# FORCE_SENSOR.net
KiCad netlist of a schematic drawn in EAGLE
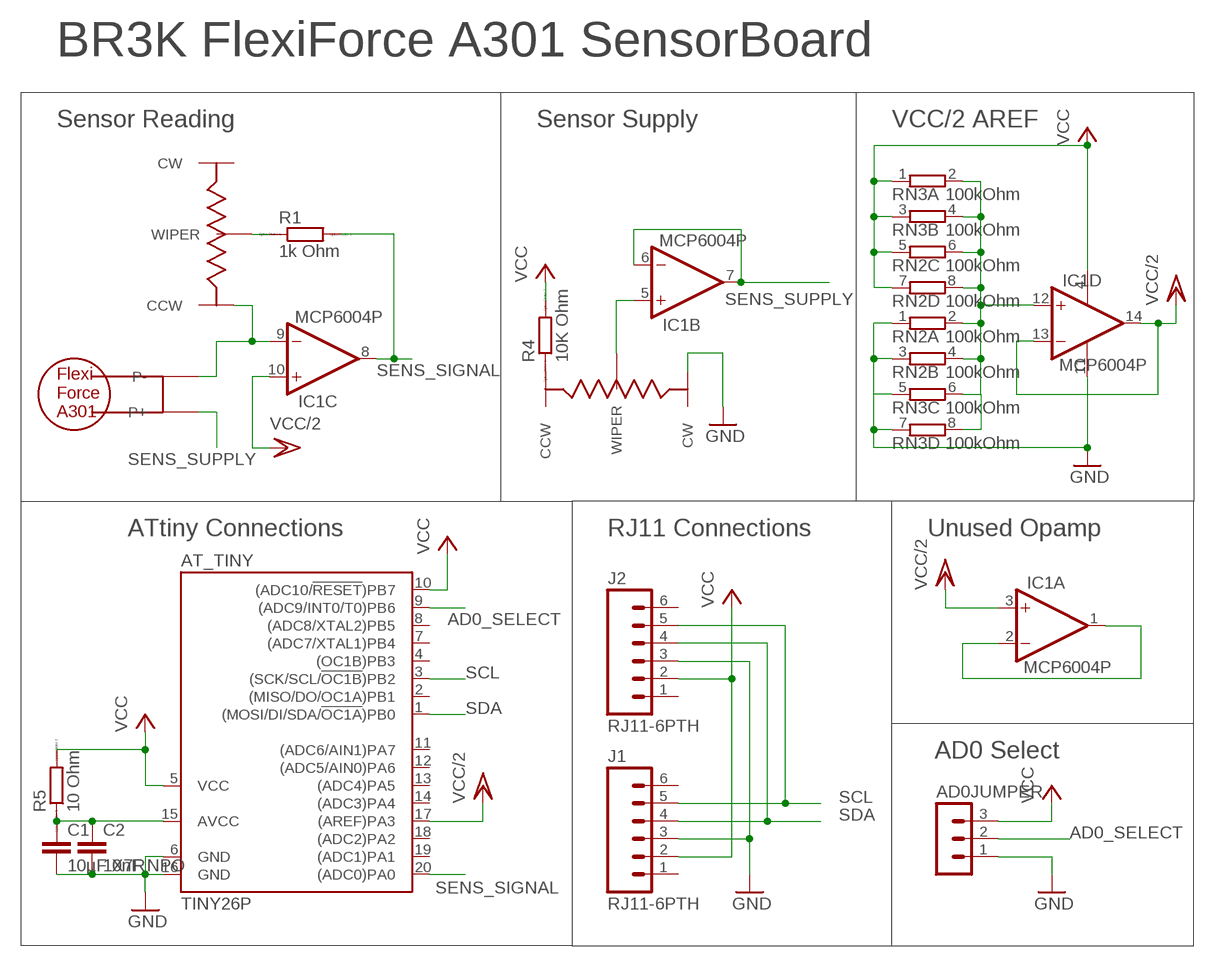
[diagram p0: schematic, sheet 1]

(export (version "E")
  (design (tool "Eeschema 10.0.6"))
  (components
    (comp (ref "AD0JUMPER")
      (value "MA03-1")
      (footprint "eagle-import:MA03-1")
      (libsource (lib "eagle-import") (part "MA03-1"))
    )
    (comp (ref "AT_TINY")
      (value "TINY26P")
      (footprint "eagle-import:DIL20")
      (fields (field (name "MPN") "ATTINY261-20PU"))
      (libsource (lib "eagle-import") (part "TINY26P"))
    )
    (comp (ref "C1")
      (value "10µF X7R")
      (footprint "eagle-import:C5B2.5")
      (libsource (lib "eagle-import") (part "C5/2.5"))
    )
    (comp (ref "C2")
      (value "10nF NPO")
      (footprint "eagle-import:C5B2.5")
      (libsource (lib "eagle-import") (part "C5/2.5"))
    )
    (comp (ref "IC1")
      (value "MCP6004P")
      (footprint "eagle-import:DIL14")
      (libsource (lib "eagle-import") (part "MCP6004P"))
    )
    (comp (ref "J1")
      (value "RJ11-6PTH")
      (footprint "eagle-import:RJ11-6")
      (libsource (lib "eagle-import") (part "RJ11-6PTH"))
    )
    (comp (ref "J2")
      (value "RJ11-6PTH")
      (footprint "eagle-import:RJ11-6")
      (libsource (lib "eagle-import") (part "RJ11-6PTH"))
    )
    (comp (ref "R1")
      (value "1k Ohm")
      (footprint "eagle-import:0207_10")
      (libsource (lib "eagle-import") (part "R-EU_0207_10"))
    )
    (comp (ref "R4")
      (value "10K Ohm")
      (footprint "eagle-import:0207_10")
      (libsource (lib "eagle-import") (part "R-EU_0207_10"))
    )
    (comp (ref "R5")
      (value "10 Ohm")
      (footprint "eagle-import:0207_10")
      (libsource (lib "eagle-import") (part "R-EU_0207_10"))
    )
    (comp (ref "RN2")
      (value "100kOhm")
      (footprint "eagle-import:SIL8")
      (libsource (lib "eagle-import") (part "E4R"))
    )
    (comp (ref "RN3")
      (value "100kOhm")
      (footprint "eagle-import:SIL8")
      (libsource (lib "eagle-import") (part "E4R"))
    )
    (comp (ref "U$1")
      (value "FLEXI_FORCE_A301")
      (footprint "eagle-import:FLEXIFORCE_W237-102")
      (libsource (lib "eagle-import") (part "FLEXI_FORCE_A301"))
    )
    (comp (ref "U$2")
      (value "100k Ohm")
      (footprint "eagle-import:VERT_TRIMPOT")
      (libsource (lib "eagle-import") (part "TRIMMER_3296"))
    )
    (comp (ref "U$3")
      (value "10k Ohm")
      (footprint "eagle-import:VERT_TRIMPOT")
      (libsource (lib "eagle-import") (part "TRIMMER_3296"))
    )
  )
  (nets
    (net (code "1") (name "/AD0_SELECT") (class "Default")
      (node (ref "AD0JUMPER") (pin "2") (pinfunction "2_2") (pintype "passive"))
      (node (ref "AT_TINY") (pin "9") (pinfunction "(ADC9/INT0/T0)PB6_9") (pintype "bidirectional"))
    )
    (net (code "2") (name "/SCL") (class "Default")
      (node (ref "AT_TINY") (pin "3") (pinfunction "(SCK/SCL/~{OC1B})PB2_3") (pintype "bidirectional"))
      (node (ref "J1") (pin "5") (pinfunction "5_5") (pintype "passive"))
      (node (ref "J2") (pin "5") (pinfunction "5_5") (pintype "passive"))
    )
    (net (code "3") (name "/SDA") (class "Default")
      (node (ref "AT_TINY") (pin "1") (pinfunction "(MOSI/DI/SDA/~{OC1A})PB0_1") (pintype "bidirectional"))
      (node (ref "J1") (pin "4") (pinfunction "4_4") (pintype "passive"))
      (node (ref "J2") (pin "4") (pinfunction "4_4") (pintype "passive"))
    )
    (net (code "4") (name "/SENS_SIGNAL") (class "Default")
      (node (ref "AT_TINY") (pin "20") (pinfunction "(ADC0)PA0_20") (pintype "bidirectional"))
      (node (ref "IC1") (pin "8") (pinfunction "OUT_8") (pintype "output"))
      (node (ref "R1") (pin "2") (pinfunction "2_2") (pintype "passive"))
    )
    (net (code "5") (name "/SENS_SUPPLY") (class "Default")
      (node (ref "IC1") (pin "6") (pinfunction "-IN_6") (pintype "input"))
      (node (ref "IC1") (pin "7") (pinfunction "OUT_7") (pintype "output"))
      (node (ref "U$1") (pin "1") (pinfunction "P+_1") (pintype "bidirectional"))
    )
    (net (code "6") (name "GND") (class "Default")
      (node (ref "AD0JUMPER") (pin "1") (pinfunction "1_1") (pintype "passive"))
      (node (ref "AT_TINY") (pin "16") (pinfunction "GND_16") (pintype "power_in"))
      (node (ref "AT_TINY") (pin "6") (pinfunction "GND_6") (pintype "power_in"))
      (node (ref "C1") (pin "2") (pinfunction "2_2") (pintype "passive"))
      (node (ref "C2") (pin "2") (pinfunction "2_2") (pintype "passive"))
      (node (ref "IC1") (pin "11") (pinfunction "V-_11") (pintype "power_in"))
      (node (ref "J1") (pin "3") (pinfunction "3_3") (pintype "passive"))
      (node (ref "J2") (pin "3") (pinfunction "3_3") (pintype "passive"))
      (node (ref "RN2") (pin "1") (pinfunction "1_1") (pintype "passive"))
      (node (ref "RN2") (pin "3") (pinfunction "1_3") (pintype "passive"))
      (node (ref "RN3") (pin "5") (pinfunction "1_5") (pintype "passive"))
      (node (ref "RN3") (pin "7") (pinfunction "1_7") (pintype "passive"))
      (node (ref "U$3") (pin "CW") (pinfunction "CW_CW") (pintype "bidirectional"))
    )
    (net (code "7") (name "Net-(AT_TINY-AVCC)") (class "Default")
      (node (ref "AT_TINY") (pin "15") (pinfunction "AVCC_15") (pintype "power_in"))
      (node (ref "C1") (pin "1") (pinfunction "1_1") (pintype "passive"))
      (node (ref "C2") (pin "1") (pinfunction "1_1") (pintype "passive"))
      (node (ref "R5") (pin "1") (pinfunction "1_1") (pintype "passive"))
    )
    (net (code "8") (name "Net-(IC1A--IN)") (class "Default")
      (node (ref "IC1") (pin "1") (pinfunction "OUT_1") (pintype "output"))
      (node (ref "IC1") (pin "2") (pinfunction "-IN_2") (pintype "input"))
    )
    (net (code "9") (name "Net-(IC1B-+IN)") (class "Default")
      (node (ref "IC1") (pin "5") (pinfunction "+IN_5") (pintype "input"))
      (node (ref "U$3") (pin "WIP") (pinfunction "WIPER_WIP") (pintype "bidirectional"))
    )
    (net (code "10") (name "Net-(IC1C--IN)") (class "Default")
      (node (ref "IC1") (pin "9") (pinfunction "-IN_9") (pintype "input"))
      (node (ref "U$1") (pin "2") (pinfunction "P-_2") (pintype "bidirectional"))
      (node (ref "U$2") (pin "CCW") (pinfunction "CCW_CCW") (pintype "bidirectional"))
    )
    (net (code "11") (name "Net-(IC1D-+IN)") (class "Default")
      (node (ref "IC1") (pin "12") (pinfunction "+IN_12") (pintype "input"))
      (node (ref "RN2") (pin "2") (pinfunction "2_2") (pintype "passive"))
      (node (ref "RN2") (pin "4") (pinfunction "2_4") (pintype "passive"))
      (node (ref "RN2") (pin "6") (pinfunction "2_6") (pintype "passive"))
      (node (ref "RN2") (pin "8") (pinfunction "2_8") (pintype "passive"))
      (node (ref "RN3") (pin "2") (pinfunction "2_2") (pintype "passive"))
      (node (ref "RN3") (pin "4") (pinfunction "2_4") (pintype "passive"))
      (node (ref "RN3") (pin "6") (pinfunction "2_6") (pintype "passive"))
      (node (ref "RN3") (pin "8") (pinfunction "2_8") (pintype "passive"))
    )
    (net (code "12") (name "Net-(R4-Pad1)") (class "Default")
      (node (ref "R4") (pin "1") (pinfunction "1_1") (pintype "passive"))
      (node (ref "U$3") (pin "CCW") (pinfunction "CCW_CCW") (pintype "bidirectional"))
    )
    (net (code "13") (name "Net-(U$2-WIPER)") (class "Default")
      (node (ref "R1") (pin "1") (pinfunction "1_1") (pintype "passive"))
      (node (ref "U$2") (pin "WIP") (pinfunction "WIPER_WIP") (pintype "bidirectional"))
    )
    (net (code "14") (name "VCC") (class "Default")
      (node (ref "AD0JUMPER") (pin "3") (pinfunction "3_3") (pintype "passive"))
      (node (ref "AT_TINY") (pin "10") (pinfunction "(ADC10/~{RESET})PB7_10") (pintype "bidirectional"))
      (node (ref "AT_TINY") (pin "5") (pinfunction "VCC_5") (pintype "power_in"))
      (node (ref "IC1") (pin "4") (pinfunction "V+_4") (pintype "power_in"))
      (node (ref "J1") (pin "2") (pinfunction "2_2") (pintype "passive"))
      (node (ref "J2") (pin "2") (pinfunction "2_2") (pintype "passive"))
      (node (ref "R4") (pin "2") (pinfunction "2_2") (pintype "passive"))
      (node (ref "R5") (pin "2") (pinfunction "2_2") (pintype "passive"))
      (node (ref "RN2") (pin "5") (pinfunction "1_5") (pintype "passive"))
      (node (ref "RN2") (pin "7") (pinfunction "1_7") (pintype "passive"))
      (node (ref "RN3") (pin "1") (pinfunction "1_1") (pintype "passive"))
      (node (ref "RN3") (pin "3") (pinfunction "1_3") (pintype "passive"))
    )
    (net (code "15") (name "VCC{slash}2") (class "Default")
      (node (ref "AT_TINY") (pin "17") (pinfunction "(AREF)PA3_17") (pintype "bidirectional"))
      (node (ref "IC1") (pin "10") (pinfunction "+IN_10") (pintype "input"))
      (node (ref "IC1") (pin "13") (pinfunction "-IN_13") (pintype "input"))
      (node (ref "IC1") (pin "14") (pinfunction "OUT_14") (pintype "output"))
      (node (ref "IC1") (pin "3") (pinfunction "+IN_3") (pintype "input"))
    )
    (net (code "16") (name "unconnected-(AT_TINY-(ADC1)PA1-Pad19)") (class "Default")
      (node (ref "AT_TINY") (pin "19") (pinfunction "(ADC1)PA1_19") (pintype "bidirectional"))
    )
    (net (code "17") (name "unconnected-(AT_TINY-(ADC2)PA2-Pad18)") (class "Default")
      (node (ref "AT_TINY") (pin "18") (pinfunction "(ADC2)PA2_18") (pintype "bidirectional"))
    )
    (net (code "18") (name "unconnected-(AT_TINY-(ADC3)PA4-Pad14)") (class "Default")
      (node (ref "AT_TINY") (pin "14") (pinfunction "(ADC3)PA4_14") (pintype "bidirectional"))
    )
    (net (code "19") (name "unconnected-(AT_TINY-(ADC4)PA5-Pad13)") (class "Default")
      (node (ref "AT_TINY") (pin "13") (pinfunction "(ADC4)PA5_13") (pintype "bidirectional"))
    )
    (net (code "20") (name "unconnected-(AT_TINY-(ADC5{slash}AIN0)PA6-Pad12)") (class "Default")
      (node (ref "AT_TINY") (pin "12") (pinfunction "(ADC5/AIN0)PA6_12") (pintype "bidirectional"))
    )
    (net (code "21") (name "unconnected-(AT_TINY-(ADC6{slash}AIN1)PA7-Pad11)") (class "Default")
      (node (ref "AT_TINY") (pin "11") (pinfunction "(ADC6/AIN1)PA7_11") (pintype "bidirectional"))
    )
    (net (code "22") (name "unconnected-(AT_TINY-(ADC7{slash}XTAL1)PB4-Pad7)") (class "Default")
      (node (ref "AT_TINY") (pin "7") (pinfunction "(ADC7/XTAL1)PB4_7") (pintype "bidirectional"))
    )
    (net (code "23") (name "unconnected-(AT_TINY-(ADC8{slash}XTAL2)PB5-Pad8)") (class "Default")
      (node (ref "AT_TINY") (pin "8") (pinfunction "(ADC8/XTAL2)PB5_8") (pintype "bidirectional"))
    )
    (net (code "24") (name "unconnected-(AT_TINY-(MISO{slash}DO{slash}OC1A)PB1-Pad2)") (class "Default")
      (node (ref "AT_TINY") (pin "2") (pinfunction "(MISO/DO/OC1A)PB1_2") (pintype "bidirectional"))
    )
    (net (code "25") (name "unconnected-(AT_TINY-(OC1B)PB3-Pad4)") (class "Default")
      (node (ref "AT_TINY") (pin "4") (pinfunction "(OC1B)PB3_4") (pintype "bidirectional"))
    )
    (net (code "26") (name "unconnected-(J1-Pad1)") (class "Default")
      (node (ref "J1") (pin "1") (pinfunction "1_1") (pintype "passive"))
    )
    (net (code "27") (name "unconnected-(J1-Pad6)") (class "Default")
      (node (ref "J1") (pin "6") (pinfunction "6_6") (pintype "passive"))
    )
    (net (code "28") (name "unconnected-(J2-Pad1)") (class "Default")
      (node (ref "J2") (pin "1") (pinfunction "1_1") (pintype "passive"))
    )
    (net (code "29") (name "unconnected-(J2-Pad6)") (class "Default")
      (node (ref "J2") (pin "6") (pinfunction "6_6") (pintype "passive"))
    )
    (net (code "30") (name "unconnected-(U$2-PadCW)") (class "Default")
      (node (ref "U$2") (pin "CW") (pinfunction "CW_CW") (pintype "bidirectional"))
    )
  )
)
